# F407.net
KiCad netlist of a schematic drawn in Altium Designer
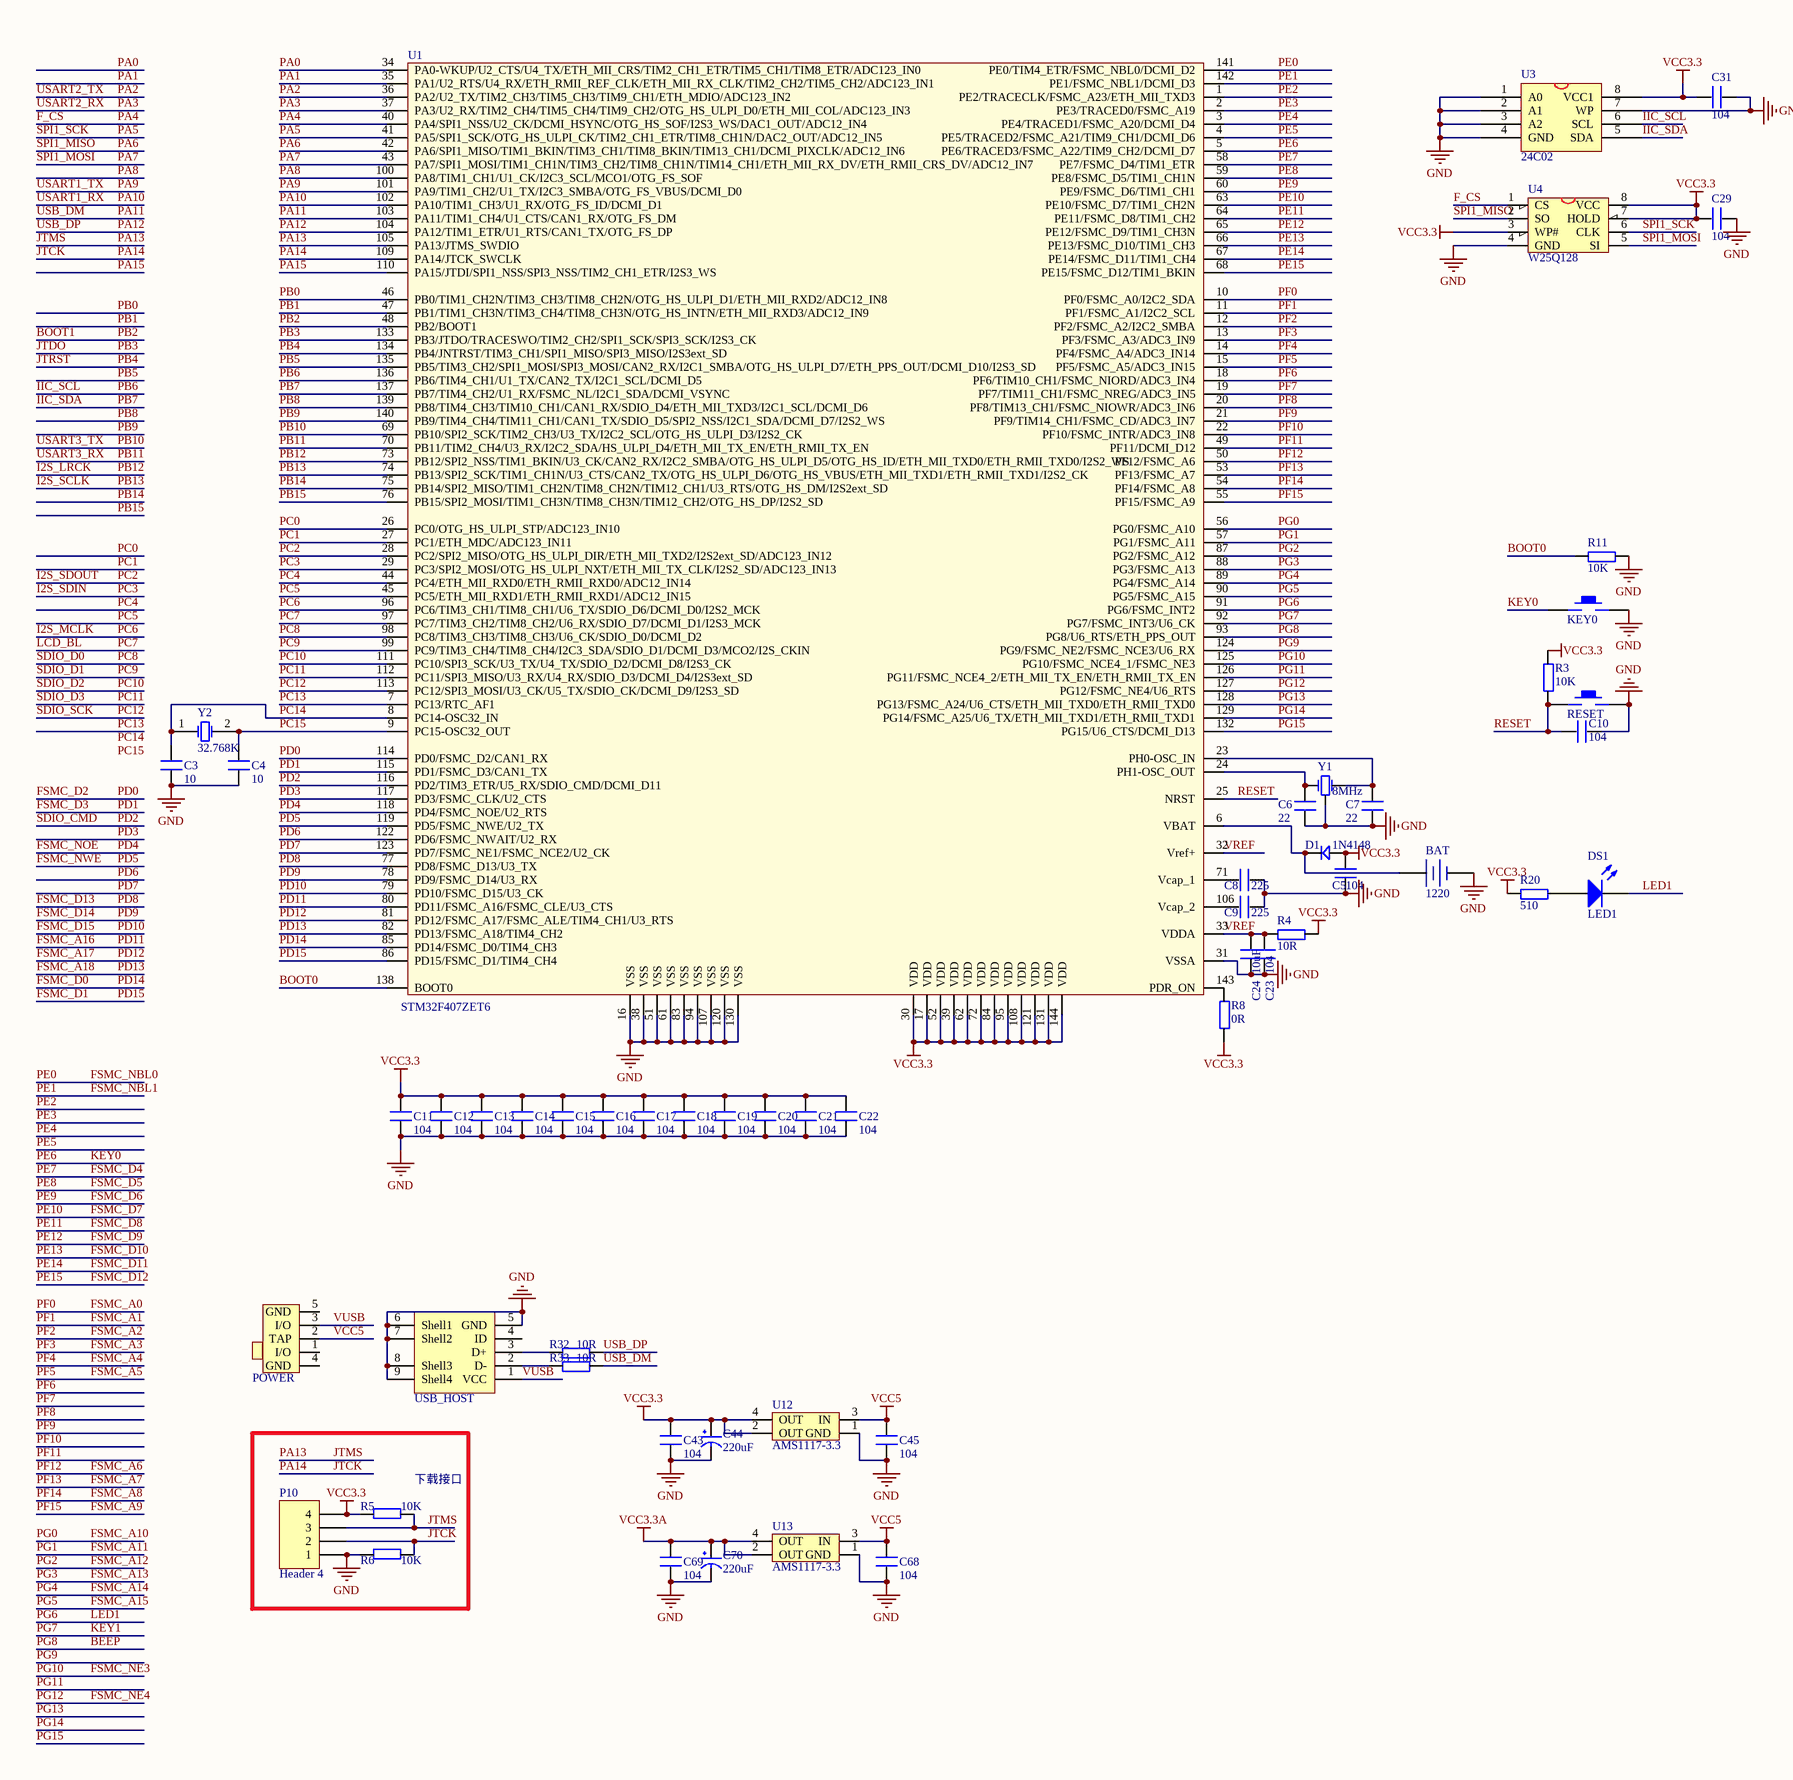
[diagram p0: F407.SchDoc, left]
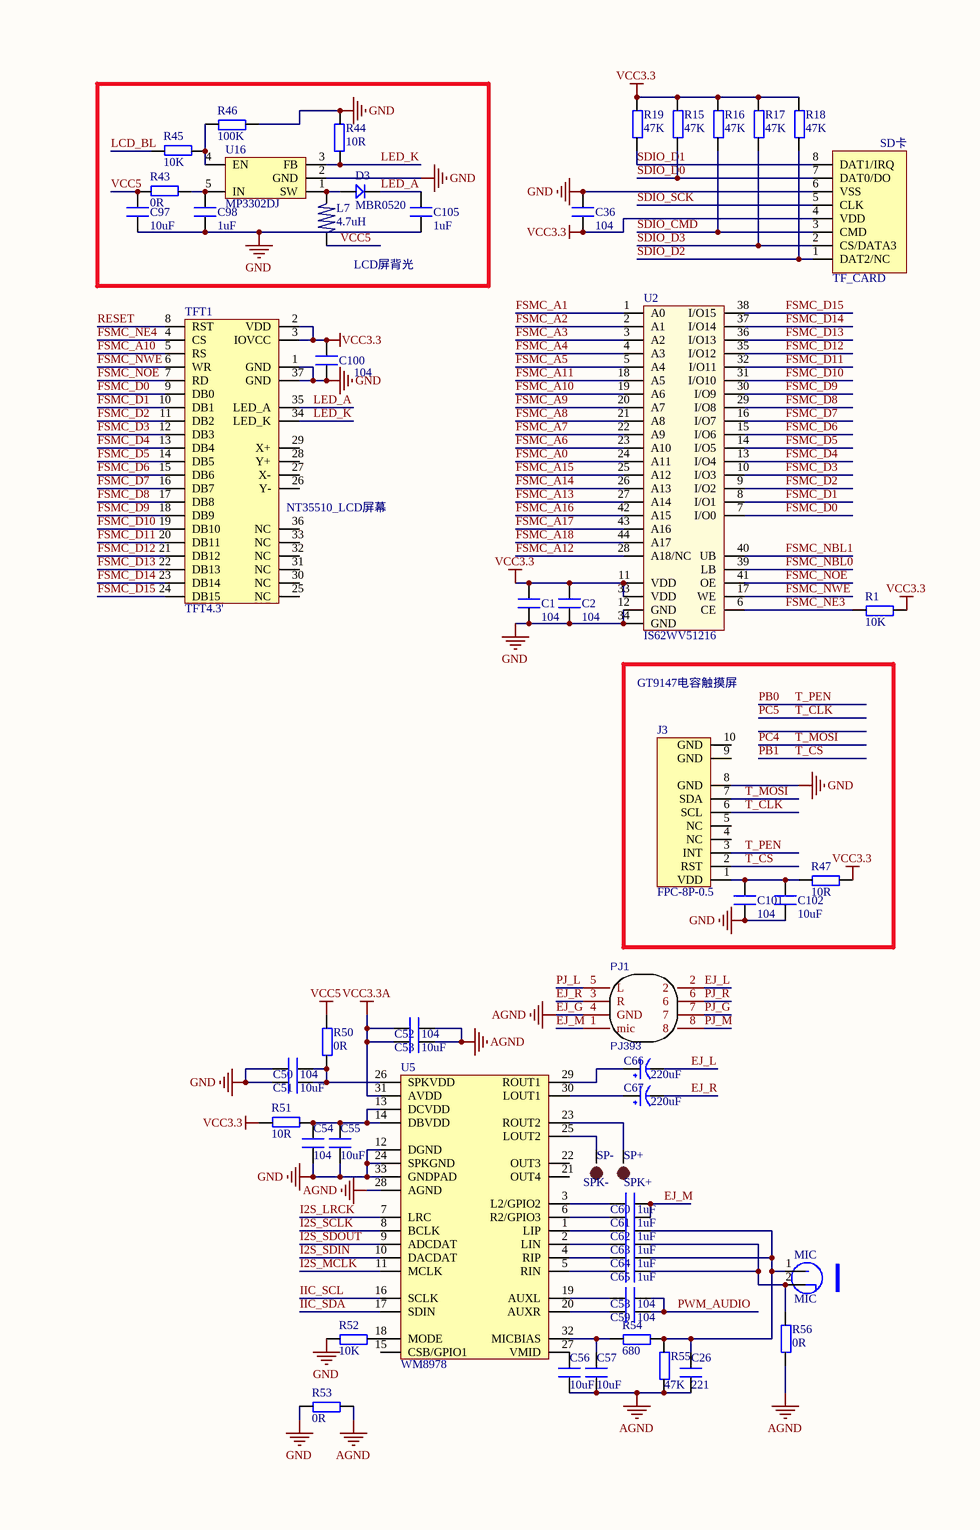
[diagram p1: F407.SchDoc, right]

(export (version "E")
  (design (tool "Eeschema 10.0.6"))
  (components
    (comp (ref "BAT")
      (value "1220")
      (footprint "CR1220_B")
      (description "微型电池")
      (libsource (lib "IMX6UL_ALPHA(底板)_V2.0") (part "CR-3V"))
    )
    (comp (ref "C1")
      (value "104")
      (footprint "C 0603_M")
      (libsource (lib "WarShip V3 STM32103封装库") (part "C"))
    )
    (comp (ref "C2")
      (value "104")
      (footprint "C 0603_M")
      (libsource (lib "WarShip V3 STM32103封装库") (part "C"))
    )
    (comp (ref "C3")
      (value "10")
      (footprint "C 0603_M")
      (libsource (lib "WarShip V3 STM32103封装库") (part "C"))
    )
    (comp (ref "C4")
      (value "10")
      (footprint "C 0603_M")
      (libsource (lib "WarShip V3 STM32103封装库") (part "C"))
    )
    (comp (ref "C5")
      (value "104")
      (footprint "C 0603_M")
      (libsource (lib "WarShip V3 STM32103封装库") (part "C"))
    )
    (comp (ref "C6")
      (value "22")
      (footprint "C 0603_M")
      (libsource (lib "WarShip V3 STM32103封装库") (part "C"))
    )
    (comp (ref "C7")
      (value "22")
      (footprint "C 0603_M")
      (libsource (lib "WarShip V3 STM32103封装库") (part "C"))
    )
    (comp (ref "C8")
      (value "225")
      (footprint "C 0603_M")
      (libsource (lib "WarShip V3 STM32103封装库") (part "C"))
    )
    (comp (ref "C9")
      (value "225")
      (footprint "C 0603_M")
      (libsource (lib "WarShip V3 STM32103封装库") (part "C"))
    )
    (comp (ref "C10")
      (value "104")
      (footprint "C 0603_M")
      (libsource (lib "WarShip V3 STM32103封装库") (part "C"))
    )
    (comp (ref "C11")
      (value "104")
      (footprint "C 0603_M")
      (libsource (lib "WarShip V3 STM32103封装库") (part "C"))
    )
    (comp (ref "C12")
      (value "104")
      (footprint "C 0603_M")
      (libsource (lib "WarShip V3 STM32103封装库") (part "C"))
    )
    (comp (ref "C13")
      (value "104")
      (footprint "C 0603_M")
      (libsource (lib "WarShip V3 STM32103封装库") (part "C"))
    )
    (comp (ref "C14")
      (value "104")
      (footprint "C 0603_M")
      (libsource (lib "WarShip V3 STM32103封装库") (part "C"))
    )
    (comp (ref "C15")
      (value "104")
      (footprint "C 0603_M")
      (libsource (lib "WarShip V3 STM32103封装库") (part "C"))
    )
    (comp (ref "C16")
      (value "104")
      (footprint "C 0603_M")
      (libsource (lib "WarShip V3 STM32103封装库") (part "C"))
    )
    (comp (ref "C17")
      (value "104")
      (footprint "C 0603_M")
      (libsource (lib "WarShip V3 STM32103封装库") (part "C"))
    )
    (comp (ref "C18")
      (value "104")
      (footprint "C 0603_M")
      (libsource (lib "WarShip V3 STM32103封装库") (part "C"))
    )
    (comp (ref "C19")
      (value "104")
      (footprint "C 0603_M")
      (libsource (lib "WarShip V3 STM32103封装库") (part "C"))
    )
    (comp (ref "C20")
      (value "104")
      (footprint "C 0603_M")
      (libsource (lib "WarShip V3 STM32103封装库") (part "C"))
    )
    (comp (ref "C21")
      (value "104")
      (footprint "C 0603_M")
      (libsource (lib "WarShip V3 STM32103封装库") (part "C"))
    )
    (comp (ref "C22")
      (value "104")
      (footprint "C 0603_M")
      (libsource (lib "WarShip V3 STM32103封装库") (part "C"))
    )
    (comp (ref "C23")
      (value "104")
      (footprint "C 0603_M")
      (libsource (lib "WarShip V3 STM32103封装库") (part "C"))
    )
    (comp (ref "C24")
      (value "10uF")
      (footprint "C 0603_M")
      (libsource (lib "WarShip V3 STM32103封装库") (part "C"))
    )
    (comp (ref "C26") (value "221") (footprint "C 0603_M") (libsource (lib "ALIENTEK_COMPONENT") (part "C")))
    (comp (ref "C29")
      (value "104")
      (footprint "C 0603_M")
      (libsource (lib "WarShip V3 STM32103封装库") (part "C"))
    )
    (comp (ref "C31")
      (value "104")
      (footprint "C 0603_M")
      (libsource (lib "WarShip V3 STM32103封装库") (part "C"))
    )
    (comp (ref "C36")
      (value "104")
      (footprint "C 0603_M")
      (libsource (lib "WarShip V3 STM32103封装库") (part "C"))
    )
    (comp (ref "C43")
      (value "104")
      (footprint "C 0603_M")
      (libsource (lib "WarShip V3 STM32103封装库") (part "C"))
    )
    (comp (ref "C44") (value "220uF") (footprint "CT 6*6 - C") (libsource (lib "") (part "CAP_1")))
    (comp (ref "C45")
      (value "104")
      (footprint "C 0603_M")
      (libsource (lib "WarShip V3 STM32103封装库") (part "C"))
    )
    (comp (ref "C50") (value "104") (footprint "C 0603_M") (libsource (lib "ATK-VS1053 MP3") (part "C")))
    (comp (ref "C51") (value "10uF") (footprint "C 0603_M") (libsource (lib "ATK-VS1053 MP3") (part "C")))
    (comp (ref "C52") (value "104") (footprint "C 0603_M") (libsource (lib "ATK-VS1053 MP3") (part "C")))
    (comp (ref "C53") (value "10uF") (footprint "C 0603_M") (libsource (lib "ATK-VS1053 MP3") (part "C")))
    (comp (ref "C54") (value "104") (footprint "C 0603_M") (libsource (lib "ATK-VS1053 MP3") (part "C")))
    (comp (ref "C55") (value "10uF") (footprint "C 0603_M") (libsource (lib "ATK-VS1053 MP3") (part "C")))
    (comp (ref "C56") (value "10uF") (footprint "C 0603_M") (libsource (lib "ATK-VS1053 MP3") (part "C")))
    (comp (ref "C57") (value "10uF") (footprint "C 0603_M") (libsource (lib "ATK-VS1053 MP3") (part "C")))
    (comp (ref "C58") (value "104") (footprint "C 0603_M") (libsource (lib "ATK-VS1053 MP3") (part "C")))
    (comp (ref "C59") (value "104") (footprint "C 0603_M") (libsource (lib "ATK-VS1053 MP3") (part "C")))
    (comp (ref "C60") (value "1uF") (footprint "C 0603_M") (libsource (lib "ATK-VS1053 MP3") (part "C")))
    (comp (ref "C61") (value "1uF") (footprint "C 0603_M") (libsource (lib "ATK-VS1053 MP3") (part "C")))
    (comp (ref "C62") (value "1uF") (footprint "C 0603_M") (libsource (lib "ATK-VS1053 MP3") (part "C")))
    (comp (ref "C63") (value "1uF") (footprint "C 0603_M") (libsource (lib "ATK-VS1053 MP3") (part "C")))
    (comp (ref "C64") (value "1uF") (footprint "C 0603_M") (libsource (lib "ATK-VS1053 MP3") (part "C")))
    (comp (ref "C65") (value "1uF") (footprint "C 0603_M") (libsource (lib "ATK-VS1053 MP3") (part "C")))
    (comp (ref "C66")
      (value "220uF")
      (footprint "CT 6*6 - C")
      (libsource (lib "WarShip V3 STM32103封装库") (part "CAP"))
    )
    (comp (ref "C67")
      (value "220uF")
      (footprint "CT 6*6 - C")
      (libsource (lib "WarShip V3 STM32103封装库") (part "CAP"))
    )
    (comp (ref "C68")
      (value "104")
      (footprint "C 0603_M")
      (libsource (lib "WarShip V3 STM32103封装库") (part "C"))
    )
    (comp (ref "C69")
      (value "104")
      (footprint "C 0603_M")
      (libsource (lib "WarShip V3 STM32103封装库") (part "C"))
    )
    (comp (ref "C70") (value "220uF") (footprint "CT 6*6 - C") (libsource (lib "") (part "CAP_1")))
    (comp (ref "C97") (value "10uF") (footprint "C 0603_M") (libsource (lib "阿波罗STM32F4&F7底板封装库") (part "C")))
    (comp (ref "C98") (value "1uF") (footprint "C 0603_M") (libsource (lib "阿波罗STM32F4&F7底板封装库") (part "C")))
    (comp (ref "C100") (value "104") (footprint "C 0603_M") (libsource (lib "阿波罗STM32F4&F7底板封装库") (part "C")))
    (comp (ref "C101") (value "104") (footprint "C 0603_M") (libsource (lib "阿波罗STM32F4&F7底板封装库") (part "C")))
    (comp (ref "C102")
      (value "10uF")
      (footprint "C 0603_M")
      (libsource (lib "阿波罗STM32F4&F7底板封装库") (part "C"))
    )
    (comp (ref "C105") (value "1uF") (footprint "C 0603_M") (libsource (lib "阿波罗STM32F4&F7底板封装库") (part "C")))
    (comp (ref "D1")
      (value "1N4148")
      (footprint "DIODE_SOP")
      (libsource (lib "WarShip V3 STM32103封装库") (part "D"))
    )
    (comp (ref "D3")
      (value "MBR0520")
      (footprint "SOD-123")
      (description "1N4148")
      (libsource (lib "ATK-4.3' TFTLCD电容触摸屏模块_V1.2") (part "D"))
    )
    (comp (ref "DS1")
      (value "LED1")
      (footprint "LED 0603R")
      (description "Typical RED, GREEN, YELLOW, AMBER GaAs LED")
      (fields (field (name "PUBLISHER") "Altium Limited"))
      (libsource (lib "WarShip V3 STM32103封装库") (part "LED2"))
    )
    (comp (ref "J3")
      (value "FPC-8P-0.5")
      (footprint "FPC-8P")
      (description "FPC-8P-0.5mm")
      (libsource (lib "ATK-4.3' TFTLCD电容触摸屏模块_V1.2") (part "FPC-8"))
    )
    (comp (ref "KEY0")
      (value "KEY_M")
      (footprint "TSW SMD-3*6*2.5")
      (libsource (lib "WarShip V3 STM32103封装库") (part "KEY_M"))
    )
    (comp (ref "L7")
      (value "4.7uH")
      (footprint "L_SOP4")
      (libsource (lib "ATK-4.3' TFTLCD电容触摸屏模块_V1.2") (part "L"))
    )
    (comp (ref "MIC")
      (value "MIC")
      (footprint "MIC-6022")
      (libsource (lib "ALIENTEK_COMPONENT") (part "MIC"))
    )
    (comp (ref "P10")
      (value "Header 4")
      (footprint "HDR2.54-LI-4P")
      (description "Header, 4-Pin")
      (fields (field (name "PUBLISHER") "Altium Limited"))
      (libsource (lib "WarShip V3 STM32103封装库") (part "Header 4"))
    )
    (comp (ref "PJ1")
      (value "PJ393")
      (footprint "PJ393")
      (fields
        (field (name "BOM_MANUFACTURER PART") "?")
        (field (name "CONTRIBUTOR") "infinite_possibilities")
      )
      (libsource (lib "PJ393") (part "PJ393"))
    )
    (comp (ref "POWER")
      (value "BUTTON_DIP3")
      (footprint "MSK-12C01-07")
      (description "拨动开关SS-12F44")
      (libsource (lib "Pandora_STM32L4_Board_V2.4") (part "BUTTON_DIP3"))
    )
    (comp (ref "R1")
      (value "10K")
      (footprint "R 0603_M")
      (libsource (lib "WarShip V3 STM32103封装库") (part "R"))
    )
    (comp (ref "R3")
      (value "10K")
      (footprint "R 0603_M")
      (libsource (lib "WarShip V3 STM32103封装库") (part "R"))
    )
    (comp (ref "R4")
      (value "10R")
      (footprint "R 0603_M")
      (libsource (lib "WarShip V3 STM32103封装库") (part "R"))
    )
    (comp (ref "R5")
      (value "10K")
      (footprint "R 0603_M")
      (libsource (lib "WarShip V3 STM32103封装库") (part "R"))
    )
    (comp (ref "R6")
      (value "10K")
      (footprint "R 0603_M")
      (libsource (lib "WarShip V3 STM32103封装库") (part "R"))
    )
    (comp (ref "R8")
      (value "0R")
      (footprint "R 0603_M")
      (libsource (lib "WarShip V3 STM32103封装库") (part "R"))
    )
    (comp (ref "R11")
      (value "10K")
      (footprint "R 0603_M")
      (libsource (lib "WarShip V3 STM32103封装库") (part "R"))
    )
    (comp (ref "R15")
      (value "47K")
      (footprint "R 0603_M")
      (libsource (lib "WarShip V3 STM32103封装库") (part "R"))
    )
    (comp (ref "R16")
      (value "47K")
      (footprint "R 0603_M")
      (libsource (lib "WarShip V3 STM32103封装库") (part "R"))
    )
    (comp (ref "R17")
      (value "47K")
      (footprint "R 0603_M")
      (libsource (lib "WarShip V3 STM32103封装库") (part "R"))
    )
    (comp (ref "R18")
      (value "47K")
      (footprint "R 0603_M")
      (libsource (lib "WarShip V3 STM32103封装库") (part "R"))
    )
    (comp (ref "R19")
      (value "47K")
      (footprint "R 0603_M")
      (libsource (lib "WarShip V3 STM32103封装库") (part "R"))
    )
    (comp (ref "R20")
      (value "510")
      (footprint "R 0603_M")
      (libsource (lib "WarShip V3 STM32103封装库") (part "R"))
    )
    (comp (ref "R32")
      (value "10R")
      (footprint "R 0603_M")
      (libsource (lib "WarShip V3 STM32103封装库") (part "R"))
    )
    (comp (ref "R33")
      (value "10R")
      (footprint "R 0603_M")
      (libsource (lib "WarShip V3 STM32103封装库") (part "R"))
    )
    (comp (ref "R43") (value "0R") (footprint "R 0603_M") (libsource (lib "阿波罗STM32F4&F7底板封装库") (part "R")))
    (comp (ref "R44") (value "10R") (footprint "R 0603_M") (libsource (lib "阿波罗STM32F4&F7底板封装库") (part "R")))
    (comp (ref "R45") (value "10K") (footprint "R 0603_M") (libsource (lib "阿波罗STM32F4&F7底板封装库") (part "R")))
    (comp (ref "R46") (value "100K") (footprint "R 0603_M") (libsource (lib "阿波罗STM32F4&F7底板封装库") (part "R")))
    (comp (ref "R47") (value "10R") (footprint "R 0603_M") (libsource (lib "阿波罗STM32F4&F7底板封装库") (part "R")))
    (comp (ref "R50") (value "0R") (footprint "R 0603_M") (libsource (lib "ATK-VS1053 MP3") (part "R")))
    (comp (ref "R51") (value "10R") (footprint "R 0603_M") (libsource (lib "ATK-VS1053 MP3") (part "R")))
    (comp (ref "R52") (value "10K") (footprint "R 0603_M") (libsource (lib "ATK-VS1053 MP3") (part "R")))
    (comp (ref "R53") (value "0R") (footprint "R 0603_M") (libsource (lib "ATK-VS1053 MP3") (part "R")))
    (comp (ref "R54") (value "680") (footprint "R 0603_M") (libsource (lib "ATK-VS1053 MP3") (part "R")))
    (comp (ref "R55") (value "47K") (footprint "R 0603_M") (libsource (lib "ATK-VS1053 MP3") (part "R")))
    (comp (ref "R56") (value "0R") (footprint "R 0603_M") (libsource (lib "ATK-VS1053 MP3") (part "R")))
    (comp (ref "RESET")
      (value "KEY_M")
      (footprint "TSW SMD-3*6*2.5")
      (libsource (lib "WarShip V3 STM32103封装库") (part "KEY_M"))
    )
    (comp (ref "SP+")
      (value "SPK+")
      (footprint "TP-1.5")
      (description "测试点")
      (libsource (lib "ALIENTEK_COMPONENT") (part "TEST-POINT"))
    )
    (comp (ref "SP-")
      (value "SPK-")
      (footprint "TP-1.5")
      (description "测试点")
      (libsource (lib "ALIENTEK_COMPONENT") (part "TEST-POINT"))
    )
    (comp (ref "TFT1")
      (value "TFT4.3'")
      (footprint "TFT4.3'")
      (description "4.3寸,电容/电阻触摸,分辨率:480*800")
      (libsource (lib "ATK-4.3' TFTLCD电容触摸屏模块_V1.2") (part "TFT4.3‘"))
    )
    (comp (ref "TF_CARD")
      (value "SD-MICRO-TF")
      (footprint "SD-MICRO-TF")
      (description "SD,MICRO,TF")
      (libsource (lib "Pandora_STM32L4_Board_V2.4") (part "SD-MICRO-TF"))
    )
    (comp (ref "U1")
      (value "STM32F407ZET6")
      (footprint "LQFP144")
      (libsource (lib "Explorer STM32F407封装库") (part "STM32F407ZET6"))
    )
    (comp (ref "U2")
      (value "IS62WV51216")
      (footprint "TSOP44")
      (libsource (lib "WarShip V3 STM32103封装库") (part "IS61LV51216"))
    )
    (comp (ref "U3")
      (value "24C02")
      (footprint "SOP-8")
      (libsource (lib "WarShip V3 STM32103封装库") (part "24C256"))
    )
    (comp (ref "U4")
      (value "W25Q128")
      (footprint "SOIC-8")
      (description "W25X16;SST25VF016;MX25L1605")
      (libsource (lib "WarShip V3 STM32103封装库") (part "W25X16"))
    )
    (comp (ref "U5")
      (value "WM8978")
      (footprint "qfn32")
      (description "24bit ADC&DAC")
      (libsource (lib "ALIENTEK_COMPONENT") (part "WM8978"))
    )
    (comp (ref "U12")
      (value "AMS1117-3.3")
      (footprint "AMS1117")
      (libsource (lib "WarShip V3 STM32103封装库") (part "AMS1117"))
    )
    (comp (ref "U13")
      (value "AMS1117-3.3")
      (footprint "AMS1117")
      (libsource (lib "WarShip V3 STM32103封装库") (part "AMS1117"))
    )
    (comp (ref "U16")
      (value "MP3302DJ")
      (footprint "SOT-23-5")
      (description "LCD背光IC")
      (libsource (lib "ATK-4.3' TFTLCD电容触摸屏模块_V1.2") (part "MP3302"))
    )
    (comp (ref "USB_HOST")
      (value "J-MICRO-USB-5S")
      (footprint "USB-AB-5S")
      (description "Micro USB 5.9有柱脚长1.25加长针")
      (libsource (lib "Pandora_STM32L4_Board_V2.4") (part "J-MICRO-USB-5S"))
    )
    (comp (ref "Y1")
      (value "8MHz")
      (footprint "Y-XTAL-3215-3P")
      (description "XTAL,3215,8MHz")
      (libsource (lib "Pandora_STM32L4_Board_V2.4") (part "Y-3215-8M"))
    )
    (comp (ref "Y2")
      (value "32.768K")
      (footprint "Y-XTAL-3215-2P")
      (description "Crystal Oscillator")
      (fields (field (name "PUBLISHER") "Altium Limited"))
      (libsource (lib "WarShip V3 STM32103封装库") (part "XTAL"))
    )
  )
  (nets
    (net (code "1") (name "/BEEP") (class "Default")
      (node (ref "U1") (pin "93") (pinfunction "PG8/U6_RTS/ETH_PPS_OUT_93") (pintype "passive"))
    )
    (net (code "2") (name "/BOOT0") (class "Default")
      (node (ref "R11") (pin "1") (pintype "passive"))
      (node (ref "U1") (pin "138") (pinfunction "BOOT0_138") (pintype "passive"))
    )
    (net (code "3") (name "/BOOT1") (class "Default")
      (node (ref "U1") (pin "48") (pinfunction "PB2/BOOT1_48") (pintype "passive"))
    )
    (net (code "4") (name "/EJ_L") (class "Default")
      (node (ref "C66") (pin "2") (pinfunction "GND_2") (pintype "passive"))
      (node (ref "PJ1") (pin "2") (pinfunction "2_2") (pintype "passive"))
    )
    (net (code "5") (name "/EJ_M") (class "Default")
      (node (ref "C60") (pin "2") (pintype "passive"))
      (node (ref "C61") (pin "2") (pintype "passive"))
      (node (ref "PJ1") (pin "1") (pinfunction "mic_1") (pintype "passive"))
    )
    (net (code "6") (name "/EJ_R") (class "Default")
      (node (ref "C67") (pin "2") (pinfunction "GND_2") (pintype "passive"))
      (node (ref "PJ1") (pin "3") (pinfunction "R_3") (pintype "passive"))
    )
    (net (code "7") (name "/FSMC_A0") (class "Default")
      (node (ref "U1") (pin "10") (pinfunction "PF0/FSMC_A0/I2C2_SDA_10") (pintype "passive"))
      (node (ref "U2") (pin "24") (pinfunction "A11_24") (pintype "passive"))
    )
    (net (code "8") (name "/FSMC_A1") (class "Default")
      (node (ref "U1") (pin "11") (pinfunction "PF1/FSMC_A1/I2C2_SCL_11") (pintype "passive"))
      (node (ref "U2") (pin "1") (pinfunction "A0_1") (pintype "passive"))
    )
    (net (code "9") (name "/FSMC_A2") (class "Default")
      (node (ref "U1") (pin "12") (pinfunction "PF2/FSMC_A2/I2C2_SMBA_12") (pintype "passive"))
      (node (ref "U2") (pin "2") (pinfunction "A1_2") (pintype "passive"))
    )
    (net (code "10") (name "/FSMC_A3") (class "Default")
      (node (ref "U1") (pin "13") (pinfunction "PF3/FSMC_A3/ADC3_IN9_13") (pintype "passive"))
      (node (ref "U2") (pin "3") (pinfunction "A2_3") (pintype "passive"))
    )
    (net (code "11") (name "/FSMC_A4") (class "Default")
      (node (ref "U1") (pin "14") (pinfunction "PF4/FSMC_A4/ADC3_IN14_14") (pintype "passive"))
      (node (ref "U2") (pin "4") (pinfunction "A3_4") (pintype "passive"))
    )
    (net (code "12") (name "/FSMC_A5") (class "Default")
      (node (ref "U1") (pin "15") (pinfunction "PF5/FSMC_A5/ADC3_IN15_15") (pintype "passive"))
      (node (ref "U2") (pin "5") (pinfunction "A4_5") (pintype "passive"))
    )
    (net (code "13") (name "/FSMC_A6") (class "Default")
      (node (ref "U1") (pin "50") (pinfunction "PF12/FSMC_A6_50") (pintype "passive"))
      (node (ref "U2") (pin "23") (pinfunction "A10_23") (pintype "passive"))
    )
    (net (code "14") (name "/FSMC_A7") (class "Default")
      (node (ref "U1") (pin "53") (pinfunction "PF13/FSMC_A7_53") (pintype "passive"))
      (node (ref "U2") (pin "22") (pinfunction "A9_22") (pintype "passive"))
    )
    (net (code "15") (name "/FSMC_A8") (class "Default")
      (node (ref "U1") (pin "54") (pinfunction "PF14/FSMC_A8_54") (pintype "passive"))
      (node (ref "U2") (pin "21") (pinfunction "A8_21") (pintype "passive"))
    )
    (net (code "16") (name "/FSMC_A9") (class "Default")
      (node (ref "U1") (pin "55") (pinfunction "PF15/FSMC_A9_55") (pintype "passive"))
      (node (ref "U2") (pin "20") (pinfunction "A7_20") (pintype "passive"))
    )
    (net (code "17") (name "/FSMC_A10") (class "Default")
      (node (ref "TFT1") (pin "5") (pinfunction "RS_5") (pintype "passive"))
      (node (ref "U1") (pin "56") (pinfunction "PG0/FSMC_A10_56") (pintype "passive"))
      (node (ref "U2") (pin "19") (pinfunction "A6_19") (pintype "passive"))
    )
    (net (code "18") (name "/FSMC_A11") (class "Default")
      (node (ref "U1") (pin "57") (pinfunction "PG1/FSMC_A11_57") (pintype "passive"))
      (node (ref "U2") (pin "18") (pinfunction "A5_18") (pintype "passive"))
    )
    (net (code "19") (name "/FSMC_A12") (class "Default")
      (node (ref "U1") (pin "87") (pinfunction "PG2/FSMC_A12_87") (pintype "passive"))
      (node (ref "U2") (pin "28") (pinfunction "A18/NC_28") (pintype "passive"))
    )
    (net (code "20") (name "/FSMC_A13") (class "Default")
      (node (ref "U1") (pin "88") (pinfunction "PG3/FSMC_A13_88") (pintype "passive"))
      (node (ref "U2") (pin "27") (pinfunction "A14_27") (pintype "passive"))
    )
    (net (code "21") (name "/FSMC_A14") (class "Default")
      (node (ref "U1") (pin "89") (pinfunction "PG4/FSMC_A14_89") (pintype "passive"))
      (node (ref "U2") (pin "26") (pinfunction "A13_26") (pintype "passive"))
    )
    (net (code "22") (name "/FSMC_A15") (class "Default")
      (node (ref "U1") (pin "90") (pinfunction "PG5/FSMC_A15_90") (pintype "passive"))
      (node (ref "U2") (pin "25") (pinfunction "A12_25") (pintype "passive"))
    )
    (net (code "23") (name "/FSMC_A16") (class "Default")
      (node (ref "U1") (pin "80") (pinfunction "PD11/FSMC_A16/FSMC_CLE/U3_CTS_80") (pintype "passive"))
      (node (ref "U2") (pin "42") (pinfunction "A15_42") (pintype "passive"))
    )
    (net (code "24") (name "/FSMC_A17") (class "Default")
      (node (ref "U1") (pin "81") (pinfunction "PD12/FSMC_A17/FSMC_ALE/TIM4_CH1/U3_RTS_81") (pintype "passive"))
      (node (ref "U2") (pin "43") (pinfunction "A16_43") (pintype "passive"))
    )
    (net (code "25") (name "/FSMC_A18") (class "Default")
      (node (ref "U1") (pin "82") (pinfunction "PD13/FSMC_A18/TIM4_CH2_82") (pintype "passive"))
      (node (ref "U2") (pin "44") (pinfunction "A17_44") (pintype "passive"))
    )
    (net (code "26") (name "/FSMC_D0") (class "Default")
      (node (ref "TFT1") (pin "9") (pinfunction "DB0_9") (pintype "passive"))
      (node (ref "U1") (pin "85") (pinfunction "PD14/FSMC_D0/TIM4_CH3_85") (pintype "passive"))
      (node (ref "U2") (pin "7") (pinfunction "I/O0_7") (pintype "passive"))
    )
    (net (code "27") (name "/FSMC_D1") (class "Default")
      (node (ref "TFT1") (pin "10") (pinfunction "DB1_10") (pintype "passive"))
      (node (ref "U1") (pin "86") (pinfunction "PD15/FSMC_D1/TIM4_CH4_86") (pintype "passive"))
      (node (ref "U2") (pin "8") (pinfunction "I/O1_8") (pintype "passive"))
    )
    (net (code "28") (name "/FSMC_D2") (class "Default")
      (node (ref "TFT1") (pin "11") (pinfunction "DB2_11") (pintype "passive"))
      (node (ref "U1") (pin "114") (pinfunction "PD0/FSMC_D2/CAN1_RX_114") (pintype "passive"))
      (node (ref "U2") (pin "9") (pinfunction "I/O2_9") (pintype "passive"))
    )
    (net (code "29") (name "/FSMC_D3") (class "Default")
      (node (ref "TFT1") (pin "12") (pinfunction "DB3_12") (pintype "passive"))
      (node (ref "U1") (pin "115") (pinfunction "PD1/FSMC_D3/CAN1_TX_115") (pintype "passive"))
      (node (ref "U2") (pin "10") (pinfunction "I/O3_10") (pintype "passive"))
    )
    (net (code "30") (name "/FSMC_D4") (class "Default")
      (node (ref "TFT1") (pin "13") (pinfunction "DB4_13") (pintype "passive"))
      (node (ref "U1") (pin "58") (pinfunction "PE7/FSMC_D4/TIM1_ETR_58") (pintype "passive"))
      (node (ref "U2") (pin "13") (pinfunction "I/O4_13") (pintype "passive"))
    )
    (net (code "31") (name "/FSMC_D5") (class "Default")
      (node (ref "TFT1") (pin "14") (pinfunction "DB5_14") (pintype "passive"))
      (node (ref "U1") (pin "59") (pinfunction "PE8/FSMC_D5/TIM1_CH1N_59") (pintype "passive"))
      (node (ref "U2") (pin "14") (pinfunction "I/O5_14") (pintype "passive"))
    )
    (net (code "32") (name "/FSMC_D6") (class "Default")
      (node (ref "TFT1") (pin "15") (pinfunction "DB6_15") (pintype "passive"))
      (node (ref "U1") (pin "60") (pinfunction "PE9/FSMC_D6/TIM1_CH1_60") (pintype "passive"))
      (node (ref "U2") (pin "15") (pinfunction "I/O6_15") (pintype "passive"))
    )
    (net (code "33") (name "/FSMC_D7") (class "Default")
      (node (ref "TFT1") (pin "16") (pinfunction "DB7_16") (pintype "passive"))
      (node (ref "U1") (pin "63") (pinfunction "PE10/FSMC_D7/TIM1_CH2N_63") (pintype "passive"))
      (node (ref "U2") (pin "16") (pinfunction "I/O7_16") (pintype "passive"))
    )
    (net (code "34") (name "/FSMC_D8") (class "Default")
      (node (ref "TFT1") (pin "17") (pinfunction "DB8_17") (pintype "passive"))
      (node (ref "U1") (pin "64") (pinfunction "PE11/FSMC_D8/TIM1_CH2_64") (pintype "passive"))
      (node (ref "U2") (pin "29") (pinfunction "I/O8_29") (pintype "passive"))
    )
    (net (code "35") (name "/FSMC_D9") (class "Default")
      (node (ref "TFT1") (pin "18") (pinfunction "DB9_18") (pintype "passive"))
      (node (ref "U1") (pin "65") (pinfunction "PE12/FSMC_D9/TIM1_CH3N_65") (pintype "passive"))
      (node (ref "U2") (pin "30") (pinfunction "I/O9_30") (pintype "passive"))
    )
    (net (code "36") (name "/FSMC_D10") (class "Default")
      (node (ref "TFT1") (pin "19") (pinfunction "DB10_19") (pintype "passive"))
      (node (ref "U1") (pin "66") (pinfunction "PE13/FSMC_D10/TIM1_CH3_66") (pintype "passive"))
      (node (ref "U2") (pin "31") (pinfunction "I/O10_31") (pintype "passive"))
    )
    (net (code "37") (name "/FSMC_D11") (class "Default")
      (node (ref "TFT1") (pin "20") (pinfunction "DB11_20") (pintype "passive"))
      (node (ref "U1") (pin "67") (pinfunction "PE14/FSMC_D11/TIM1_CH4_67") (pintype "passive"))
      (node (ref "U2") (pin "32") (pinfunction "I/O11_32") (pintype "passive"))
    )
    (net (code "38") (name "/FSMC_D12") (class "Default")
      (node (ref "TFT1") (pin "21") (pinfunction "DB12_21") (pintype "passive"))
      (node (ref "U1") (pin "68") (pinfunction "PE15/FSMC_D12/TIM1_BKIN_68") (pintype "passive"))
      (node (ref "U2") (pin "35") (pinfunction "I/O12_35") (pintype "passive"))
    )
    (net (code "39") (name "/FSMC_D13") (class "Default")
      (node (ref "TFT1") (pin "22") (pinfunction "DB13_22") (pintype "passive"))
      (node (ref "U1") (pin "77") (pinfunction "PD8/FSMC_D13/U3_TX_77") (pintype "passive"))
      (node (ref "U2") (pin "36") (pinfunction "I/O13_36") (pintype "passive"))
    )
    (net (code "40") (name "/FSMC_D14") (class "Default")
      (node (ref "TFT1") (pin "23") (pinfunction "DB14_23") (pintype "passive"))
      (node (ref "U1") (pin "78") (pinfunction "PD9/FSMC_D14/U3_RX_78") (pintype "passive"))
      (node (ref "U2") (pin "37") (pinfunction "I/O14_37") (pintype "passive"))
    )
    (net (code "41") (name "/FSMC_D15") (class "Default")
      (node (ref "TFT1") (pin "24") (pinfunction "DB15_24") (pintype "passive"))
      (node (ref "U1") (pin "79") (pinfunction "PD10/FSMC_D15/U3_CK_79") (pintype "passive"))
      (node (ref "U2") (pin "38") (pinfunction "I/O15_38") (pintype "passive"))
    )
    (net (code "42") (name "/FSMC_NBL0") (class "Default")
      (node (ref "U1") (pin "141") (pinfunction "PE0/TIM4_ETR/FSMC_NBL0/DCMI_D2_141") (pintype "passive"))
      (node (ref "U2") (pin "39") (pinfunction "LB_39") (pintype "passive"))
    )
    (net (code "43") (name "/FSMC_NBL1") (class "Default")
      (node (ref "U1") (pin "142") (pinfunction "PE1/FSMC_NBL1/DCMI_D3_142") (pintype "passive"))
      (node (ref "U2") (pin "40") (pinfunction "UB_40") (pintype "passive"))
    )
    (net (code "44") (name "/FSMC_NE3") (class "Default")
      (node (ref "R1") (pin "1") (pintype "passive"))
      (node (ref "U1") (pin "125") (pinfunction "PG10/FSMC_NCE4_1/FSMC_NE3_125") (pintype "passive"))
      (node (ref "U2") (pin "6") (pinfunction "CE_6") (pintype "passive"))
    )
    (net (code "45") (name "/FSMC_NE4") (class "Default")
      (node (ref "TFT1") (pin "4") (pinfunction "CS_4") (pintype "passive"))
      (node (ref "U1") (pin "127") (pinfunction "PG12/FSMC_NE4/U6_RTS_127") (pintype "passive"))
    )
    (net (code "46") (name "/FSMC_NOE") (class "Default")
      (node (ref "TFT1") (pin "7") (pinfunction "RD_7") (pintype "passive"))
      (node (ref "U1") (pin "118") (pinfunction "PD4/FSMC_NOE/U2_RTS_118") (pintype "passive"))
      (node (ref "U2") (pin "41") (pinfunction "OE_41") (pintype "passive"))
    )
    (net (code "47") (name "/FSMC_NWE") (class "Default")
      (node (ref "TFT1") (pin "6") (pinfunction "WR_6") (pintype "passive"))
      (node (ref "U1") (pin "119") (pinfunction "PD5/FSMC_NWE/U2_TX_119") (pintype "passive"))
      (node (ref "U2") (pin "17") (pinfunction "WE_17") (pintype "passive"))
    )
    (net (code "48") (name "/F_CS") (class "Default")
      (node (ref "U1") (pin "40") (pinfunction "PA4/SPI1_NSS/U2_CK/DCMI_HSYNC/OTG_HS_SOF/I2S3_WS/DAC1_OUT/ADC12_IN4_40") (pintype "passive"))
      (node (ref "U4") (pin "1") (pinfunction "CS_1") (pintype "passive"))
    )
    (net (code "49") (name "/I2S_LRCK") (class "Default")
      (node (ref "U1") (pin "73") (pinfunction "PB12/SPI2_NSS/TIM1_BKIN/U3_CK/CAN2_RX/I2C2_SMBA/OTG_HS_ULPI_D5/OTG_HS_ID/ETH_MII_TXD0/ETH_RMII_TXD0/I2S2_WS_73") (pintype "passive"))
      (node (ref "U5") (pin "7") (pinfunction "LRC_7") (pintype "passive"))
    )
    (net (code "50") (name "/I2S_MCLK") (class "Default")
      (node (ref "U1") (pin "96") (pinfunction "PC6/TIM3_CH1/TIM8_CH1/U6_TX/SDIO_D6/DCMI_D0/I2S2_MCK_96") (pintype "passive"))
      (node (ref "U5") (pin "11") (pinfunction "MCLK_11") (pintype "passive"))
    )
    (net (code "51") (name "/I2S_SCLK") (class "Default")
      (node (ref "U1") (pin "74") (pinfunction "PB13/SPI2_SCK/TIM1_CH1N/U3_CTS/CAN2_TX/OTG_HS_ULPI_D6/OTG_HS_VBUS/ETH_MII_TXD1/ETH_RMII_TXD1/I2S2_CK_74") (pintype "passive"))
      (node (ref "U5") (pin "8") (pinfunction "BCLK_8") (pintype "passive"))
    )
    (net (code "52") (name "/I2S_SDIN") (class "Default")
      (node (ref "U1") (pin "29") (pinfunction "PC3/SPI2_MOSI/OTG_HS_ULPI_NXT/ETH_MII_TX_CLK/I2S2_SD/ADC123_IN13_29") (pintype "passive"))
      (node (ref "U5") (pin "10") (pinfunction "DACDAT_10") (pintype "passive"))
    )
    (net (code "53") (name "/I2S_SDOUT") (class "Default")
      (node (ref "U1") (pin "28") (pinfunction "PC2/SPI2_MISO/OTG_HS_ULPI_DIR/ETH_MII_TXD2/I2S2ext_SD/ADC123_IN12_28") (pintype "passive"))
      (node (ref "U5") (pin "9") (pinfunction "ADCDAT_9") (pintype "passive"))
    )
    (net (code "54") (name "/IIC_SCL") (class "Default")
      (node (ref "U1") (pin "136") (pinfunction "PB6/TIM4_CH1/U1_TX/CAN2_TX/I2C1_SCL/DCMI_D5_136") (pintype "passive"))
      (node (ref "U3") (pin "6") (pinfunction "SCL_6") (pintype "passive"))
      (node (ref "U5") (pin "16") (pinfunction "SCLK_16") (pintype "passive"))
    )
    (net (code "55") (name "/IIC_SDA") (class "Default")
      (node (ref "U1") (pin "137") (pinfunction "PB7/TIM4_CH2/U1_RX/FSMC_NL/I2C1_SDA/DCMI_VSYNC_137") (pintype "passive"))
      (node (ref "U3") (pin "5") (pinfunction "SDA_5") (pintype "passive"))
      (node (ref "U5") (pin "17") (pinfunction "SDIN_17") (pintype "passive"))
    )
    (net (code "56") (name "/JTCK") (class "Default")
      (node (ref "P10") (pin "2") (pinfunction "2_2") (pintype "passive"))
      (node (ref "R6") (pin "1") (pintype "passive"))
      (node (ref "U1") (pin "109") (pinfunction "PA14/JTCK_SWCLK_109") (pintype "passive"))
    )
    (net (code "57") (name "/JTDO") (class "Default")
      (node (ref "U1") (pin "133") (pinfunction "PB3/JTDO/TRACESWO/TIM2_CH2/SPI1_SCK/SPI3_SCK/I2S3_CK_133") (pintype "passive"))
    )
    (net (code "58") (name "/JTMS") (class "Default")
      (node (ref "P10") (pin "3") (pinfunction "3_3") (pintype "passive"))
      (node (ref "R5") (pin "1") (pintype "passive"))
      (node (ref "U1") (pin "105") (pinfunction "PA13/JTMS_SWDIO_105") (pintype "passive"))
    )
    (net (code "59") (name "/JTRST") (class "Default")
      (node (ref "U1") (pin "134") (pinfunction "PB4/JNTRST/TIM3_CH1/SPI1_MISO/SPI3_MISO/I2S3ext_SD_134") (pintype "passive"))
    )
    (net (code "60") (name "/KEY0") (class "Default")
      (node (ref "KEY0") (pin "1") (pinfunction "1_1") (pintype "passive"))
      (node (ref "U1") (pin "5") (pinfunction "PE6/TRACED3/FSMC_A22/TIM9_CH2/DCMI_D7_5") (pintype "passive"))
    )
    (net (code "61") (name "/KEY1") (class "Default")
      (node (ref "U1") (pin "92") (pinfunction "PG7/FSMC_INT3/U6_CK_92") (pintype "passive"))
    )
    (net (code "62") (name "/LCD_BL") (class "Default")
      (node (ref "R45") (pin "2") (pintype "passive"))
      (node (ref "U1") (pin "97") (pinfunction "PC7/TIM3_CH2/TIM8_CH2/U6_RX/SDIO_D7/DCMI_D1/I2S3_MCK_97") (pintype "passive"))
    )
    (net (code "63") (name "/LED1") (class "Default")
      (node (ref "DS1") (pin "2") (pinfunction "K_2") (pintype "passive"))
      (node (ref "U1") (pin "91") (pinfunction "PG6/FSMC_INT2_91") (pintype "passive"))
    )
    (net (code "64") (name "/LED_A") (class "Default")
      (node (ref "C105") (pin "1") (pintype "passive"))
      (node (ref "D3") (pin "2") (pintype "passive"))
      (node (ref "TFT1") (pin "35") (pinfunction "LED_A_35") (pintype "passive"))
    )
    (net (code "65") (name "/LED_K") (class "Default")
      (node (ref "R44") (pin "2") (pintype "passive"))
      (node (ref "TFT1") (pin "34") (pinfunction "LED_K_34") (pintype "passive"))
      (node (ref "U16") (pin "3") (pinfunction "FB_3") (pintype "passive"))
    )
    (net (code "66") (name "/PA0") (class "Default")
      (node (ref "U1") (pin "34") (pinfunction "PA0-WKUP/U2_CTS/U4_TX/ETH_MII_CRS/TIM2_CH1_ETR/TIM5_CH1/TIM8_ETR/ADC123_IN0_34") (pintype "passive"))
    )
    (net (code "67") (name "/PA1") (class "Default")
      (node (ref "U1") (pin "35") (pinfunction "PA1/U2_RTS/U4_RX/ETH_RMII_REF_CLK/ETH_MII_RX_CLK/TIM2_CH2/TIM5_CH2/ADC123_IN1_35") (pintype "passive"))
    )
    (net (code "68") (name "/PA2") (class "Default")
      (node (ref "U1") (pin "36") (pinfunction "PA2/U2_TX/TIM2_CH3/TIM5_CH3/TIM9_CH1/ETH_MDIO/ADC123_IN2_36") (pintype "passive"))
    )
    (net (code "69") (name "/PA3") (class "Default")
      (node (ref "U1") (pin "37") (pinfunction "PA3/U2_RX/TIM2_CH4/TIM5_CH4/TIM9_CH2/OTG_HS_ULPI_D0/ETH_MII_COL/ADC123_IN3_37") (pintype "passive"))
    )
    (net (code "70") (name "/PA5") (class "Default")
      (node (ref "U1") (pin "41") (pinfunction "PA5/SPI1_SCK/OTG_HS_ULPI_CK/TIM2_CH1_ETR/TIM8_CH1N/DAC2_OUT/ADC12_IN5_41") (pintype "passive"))
      (node (ref "U4") (pin "6") (pinfunction "CLK_6") (pintype "passive"))
    )
    (net (code "71") (name "/PA6") (class "Default")
      (node (ref "U1") (pin "42") (pinfunction "PA6/SPI1_MISO/TIM1_BKIN/TIM3_CH1/TIM8_BKIN/TIM13_CH1/DCMI_PIXCLK/ADC12_IN6_42") (pintype "passive"))
      (node (ref "U4") (pin "2") (pinfunction "SO_2") (pintype "passive"))
    )
    (net (code "72") (name "/PA7") (class "Default")
      (node (ref "U1") (pin "43") (pinfunction "PA7/SPI1_MOSI/TIM1_CH1N/TIM3_CH2/TIM8_CH1N/TIM14_CH1/ETH_MII_RX_DV/ETH_RMII_CRS_DV/ADC12_IN7_43") (pintype "passive"))
      (node (ref "U4") (pin "5") (pinfunction "SI_5") (pintype "passive"))
    )
    (net (code "73") (name "/PA8") (class "Default")
      (node (ref "U1") (pin "100") (pinfunction "PA8/TIM1_CH1/U1_CK/I2C3_SCL/MCO1/OTG_FS_SOF_100") (pintype "passive"))
    )
    (net (code "74") (name "/PA9") (class "Default")
      (node (ref "U1") (pin "101") (pinfunction "PA9/TIM1_CH2/U1_TX/I2C3_SMBA/OTG_FS_VBUS/DCMI_D0_101") (pintype "passive"))
    )
    (net (code "75") (name "/PA10") (class "Default")
      (node (ref "U1") (pin "102") (pinfunction "PA10/TIM1_CH3/U1_RX/OTG_FS_ID/DCMI_D1_102") (pintype "passive"))
    )
    (net (code "76") (name "/PA11") (class "Default")
      (node (ref "R33") (pin "2") (pintype "passive"))
      (node (ref "U1") (pin "103") (pinfunction "PA11/TIM1_CH4/U1_CTS/CAN1_RX/OTG_FS_DM_103") (pintype "passive"))
    )
    (net (code "77") (name "/PA12") (class "Default")
      (node (ref "R32") (pin "2") (pintype "passive"))
      (node (ref "U1") (pin "104") (pinfunction "PA12/TIM1_ETR/U1_RTS/CAN1_TX/OTG_FS_DP_104") (pintype "passive"))
    )
    (net (code "78") (name "/PA15") (class "Default")
      (node (ref "U1") (pin "110") (pinfunction "PA15/JTDI/SPI1_NSS/SPI3_NSS/TIM2_CH1_ETR/I2S3_WS_110") (pintype "passive"))
    )
    (net (code "79") (name "/PB0") (class "Default")
      (node (ref "J3") (pin "3") (pinfunction "INT_3") (pintype "passive"))
      (node (ref "U1") (pin "46") (pinfunction "PB0/TIM1_CH2N/TIM3_CH3/TIM8_CH2N/OTG_HS_ULPI_D1/ETH_MII_RXD2/ADC12_IN8_46") (pintype "passive"))
    )
    (net (code "80") (name "/PB1") (class "Default")
      (node (ref "J3") (pin "2") (pinfunction "RST_2") (pintype "passive"))
      (node (ref "U1") (pin "47") (pinfunction "PB1/TIM1_CH3N/TIM3_CH4/TIM8_CH3N/OTG_HS_INTN/ETH_MII_RXD3/ADC12_IN9_47") (pintype "passive"))
    )
    (net (code "81") (name "/PB5") (class "Default")
      (node (ref "U1") (pin "135") (pinfunction "PB5/TIM3_CH2/SPI1_MOSI/SPI3_MOSI/CAN2_RX/I2C1_SMBA/OTG_HS_ULPI_D7/ETH_PPS_OUT/DCMI_D10/I2S3_SD_135") (pintype "passive"))
    )
    (net (code "82") (name "/PB8") (class "Default")
      (node (ref "U1") (pin "139") (pinfunction "PB8/TIM4_CH3/TIM10_CH1/CAN1_RX/SDIO_D4/ETH_MII_TXD3/I2C1_SCL/DCMI_D6_139") (pintype "passive"))
    )
    (net (code "83") (name "/PB9") (class "Default")
      (node (ref "U1") (pin "140") (pinfunction "PB9/TIM4_CH4/TIM11_CH1/CAN1_TX/SDIO_D5/SPI2_NSS/I2C1_SDA/DCMI_D7/I2S2_WS_140") (pintype "passive"))
    )
    (net (code "84") (name "/PB10") (class "Default")
      (node (ref "U1") (pin "69") (pinfunction "PB10/SPI2_SCK/TIM2_CH3/U3_TX/I2C2_SCL/OTG_HS_ULPI_D3/I2S2_CK_69") (pintype "passive"))
    )
    (net (code "85") (name "/PB11") (class "Default")
      (node (ref "U1") (pin "70") (pinfunction "PB11/TIM2_CH4/U3_RX/I2C2_SDA/HS_ULPI_D4/ETH_MII_TX_EN/ETH_RMII_TX_EN_70") (pintype "passive"))
    )
    (net (code "86") (name "/PB14") (class "Default")
      (node (ref "U1") (pin "75") (pinfunction "PB14/SPI2_MISO/TIM1_CH2N/TIM8_CH2N/TIM12_CH1/U3_RTS/OTG_HS_DM/I2S2ext_SD_75") (pintype "passive"))
    )
    (net (code "87") (name "/PB15") (class "Default")
      (node (ref "U1") (pin "76") (pinfunction "PB15/SPI2_MOSI/TIM1_CH3N/TIM8_CH3N/TIM12_CH2/OTG_HS_DP/I2S2_SD_76") (pintype "passive"))
    )
    (net (code "88") (name "/PC0") (class "Default")
      (node (ref "U1") (pin "26") (pinfunction "PC0/OTG_HS_ULPI_STP/ADC123_IN10_26") (pintype "passive"))
    )
    (net (code "89") (name "/PC1") (class "Default")
      (node (ref "U1") (pin "27") (pinfunction "PC1/ETH_MDC/ADC123_IN11_27") (pintype "passive"))
    )
    (net (code "90") (name "/PC4") (class "Default")
      (node (ref "J3") (pin "7") (pinfunction "SDA_7") (pintype "passive"))
      (node (ref "U1") (pin "44") (pinfunction "PC4/ETH_MII_RXD0/ETH_RMII_RXD0/ADC12_IN14_44") (pintype "passive"))
    )
    (net (code "91") (name "/PC5") (class "Default")
      (node (ref "J3") (pin "6") (pinfunction "SCL_6") (pintype "passive"))
      (node (ref "U1") (pin "45") (pinfunction "PC5/ETH_MII_RXD1/ETH_RMII_RXD1/ADC12_IN15_45") (pintype "passive"))
    )
    (net (code "92") (name "/PC8") (class "Default")
      (node (ref "R15") (pin "1") (pintype "passive"))
      (node (ref "TF_CARD") (pin "7") (pinfunction "DAT0/DO_7") (pintype "passive"))
      (node (ref "U1") (pin "98") (pinfunction "PC8/TIM3_CH3/TIM8_CH3/U6_CK/SDIO_D0/DCMI_D2_98") (pintype "passive"))
    )
    (net (code "93") (name "/PC9") (class "Default")
      (node (ref "R19") (pin "1") (pintype "passive"))
      (node (ref "TF_CARD") (pin "8") (pinfunction "DAT1/IRQ_8") (pintype "passive"))
      (node (ref "U1") (pin "99") (pinfunction "PC9/TIM3_CH4/TIM8_CH4/I2C3_SDA/SDIO_D1/DCMI_D3/MCO2/I2S_CKIN_99") (pintype "passive"))
    )
    (net (code "94") (name "/PC10") (class "Default")
      (node (ref "R18") (pin "1") (pintype "passive"))
      (node (ref "TF_CARD") (pin "1") (pinfunction "DAT2/NC_1") (pintype "passive"))
      (node (ref "U1") (pin "111") (pinfunction "PC10/SPI3_SCK/U3_TX/U4_TX/SDIO_D2/DCMI_D8/I2S3_CK_111") (pintype "passive"))
    )
    (net (code "95") (name "/PC11") (class "Default")
      (node (ref "R17") (pin "1") (pintype "passive"))
      (node (ref "TF_CARD") (pin "2") (pinfunction "CS/DATA3_2") (pintype "passive"))
      (node (ref "U1") (pin "112") (pinfunction "PC11/SPI3_MISO/U3_RX/U4_RX/SDIO_D3/DCMI_D4/I2S3ext_SD_112") (pintype "passive"))
    )
    (net (code "96") (name "/PC12") (class "Default")
      (node (ref "TF_CARD") (pin "5") (pinfunction "CLK_5") (pintype "passive"))
      (node (ref "U1") (pin "113") (pinfunction "PC12/SPI3_MOSI/U3_CK/U5_TX/SDIO_CK/DCMI_D9/I2S3_SD_113") (pintype "passive"))
    )
    (net (code "97") (name "/PC13") (class "Default")
      (node (ref "U1") (pin "7") (pinfunction "PC13/RTC_AF1_7") (pintype "passive"))
    )
    (net (code "98") (name "/PC14") (class "Default")
      (node (ref "C3") (pin "2") (pintype "passive"))
      (node (ref "U1") (pin "8") (pinfunction "PC14-OSC32_IN_8") (pintype "passive"))
      (node (ref "Y2") (pin "1") (pinfunction "OSC1_1") (pintype "passive"))
    )
    (net (code "99") (name "/PC15") (class "Default")
      (node (ref "C4") (pin "1") (pintype "passive"))
      (node (ref "U1") (pin "9") (pinfunction "PC15-OSC32_OUT_9") (pintype "passive"))
      (node (ref "Y2") (pin "2") (pinfunction "OSC2_2") (pintype "passive"))
    )
    (net (code "100") (name "/PD2") (class "Default")
      (node (ref "R16") (pin "1") (pintype "passive"))
      (node (ref "TF_CARD") (pin "3") (pinfunction "CMD_3") (pintype "passive"))
      (node (ref "U1") (pin "116") (pinfunction "PD2/TIM3_ETR/U5_RX/SDIO_CMD/DCMI_D11_116") (pintype "passive"))
    )
    (net (code "101") (name "/PD3") (class "Default")
      (node (ref "U1") (pin "117") (pinfunction "PD3/FSMC_CLK/U2_CTS_117") (pintype "passive"))
    )
    (net (code "102") (name "/PD6") (class "Default")
      (node (ref "U1") (pin "122") (pinfunction "PD6/FSMC_NWAIT/U2_RX_122") (pintype "passive"))
    )
    (net (code "103") (name "/PD7") (class "Default")
      (node (ref "U1") (pin "123") (pinfunction "PD7/FSMC_NE1/FSMC_NCE2/U2_CK_123") (pintype "passive"))
    )
    (net (code "104") (name "/PE2") (class "Default")
      (node (ref "U1") (pin "1") (pinfunction "PE2/TRACECLK/FSMC_A23/ETH_MII_TXD3_1") (pintype "passive"))
    )
    (net (code "105") (name "/PE3") (class "Default")
      (node (ref "U1") (pin "2") (pinfunction "PE3/TRACED0/FSMC_A19_2") (pintype "passive"))
    )
    (net (code "106") (name "/PE4") (class "Default")
      (node (ref "U1") (pin "3") (pinfunction "PE4/TRACED1/FSMC_A20/DCMI_D4_3") (pintype "passive"))
    )
    (net (code "107") (name "/PE5") (class "Default")
      (node (ref "U1") (pin "4") (pinfunction "PE5/TRACED2/FSMC_A21/TIM9_CH1/DCMI_D6_4") (pintype "passive"))
    )
    (net (code "108") (name "/PF6") (class "Default")
      (node (ref "U1") (pin "18") (pinfunction "PF6/TIM10_CH1/FSMC_NIORD/ADC3_IN4_18") (pintype "passive"))
    )
    (net (code "109") (name "/PF7") (class "Default")
      (node (ref "U1") (pin "19") (pinfunction "PF7/TIM11_CH1/FSMC_NREG/ADC3_IN5_19") (pintype "passive"))
    )
    (net (code "110") (name "/PF8") (class "Default")
      (node (ref "U1") (pin "20") (pinfunction "PF8/TIM13_CH1/FSMC_NIOWR/ADC3_IN6_20") (pintype "passive"))
    )
    (net (code "111") (name "/PF9") (class "Default")
      (node (ref "U1") (pin "21") (pinfunction "PF9/TIM14_CH1/FSMC_CD/ADC3_IN7_21") (pintype "passive"))
    )
    (net (code "112") (name "/PF10") (class "Default")
      (node (ref "U1") (pin "22") (pinfunction "PF10/FSMC_INTR/ADC3_IN8_22") (pintype "passive"))
    )
    (net (code "113") (name "/PF11") (class "Default")
      (node (ref "U1") (pin "49") (pinfunction "PF11/DCMI_D12_49") (pintype "passive"))
    )
    (net (code "114") (name "/PG9") (class "Default")
      (node (ref "U1") (pin "124") (pinfunction "PG9/FSMC_NE2/FSMC_NCE3/U6_RX_124") (pintype "passive"))
    )
    (net (code "115") (name "/PG11") (class "Default")
      (node (ref "U1") (pin "126") (pinfunction "PG11/FSMC_NCE4_2/ETH_MII_TX_EN/ETH_RMII_TX_EN_126") (pintype "passive"))
    )
    (net (code "116") (name "/PG13") (class "Default")
      (node (ref "U1") (pin "128") (pinfunction "PG13/FSMC_A24/U6_CTS/ETH_MII_TXD0/ETH_RMII_TXD0_128") (pintype "passive"))
    )
    (net (code "117") (name "/PG14") (class "Default")
      (node (ref "U1") (pin "129") (pinfunction "PG14/FSMC_A25/U6_TX/ETH_MII_TXD1/ETH_RMII_TXD1_129") (pintype "passive"))
    )
    (net (code "118") (name "/PG15") (class "Default")
      (node (ref "U1") (pin "132") (pinfunction "PG15/U6_CTS/DCMI_D13_132") (pintype "passive"))
    )
    (net (code "119") (name "/PJ_G") (class "Default")
      (node (ref "PJ1") (pin "7") (pinfunction "7_7") (pintype "passive"))
    )
    (net (code "120") (name "/PJ_L") (class "Default")
      (node (ref "PJ1") (pin "5") (pinfunction "L_5") (pintype "passive"))
    )
    (net (code "121") (name "/PJ_M") (class "Default")
      (node (ref "PJ1") (pin "8") (pinfunction "8_8") (pintype "passive"))
    )
    (net (code "122") (name "/PJ_R") (class "Default")
      (node (ref "PJ1") (pin "6") (pinfunction "6_6") (pintype "passive"))
    )
    (net (code "123") (name "/PWM_AUDIO") (class "Default")
      (node (ref "C58") (pin "2") (pintype "passive"))
      (node (ref "C59") (pin "2") (pintype "passive"))
    )
    (net (code "124") (name "/RESET") (class "Default")
      (node (ref "C10") (pin "2") (pintype "passive"))
      (node (ref "R3") (pin "1") (pintype "passive"))
      (node (ref "RESET") (pin "1") (pinfunction "1_1") (pintype "passive"))
      (node (ref "TFT1") (pin "8") (pinfunction "RST_8") (pintype "passive"))
      (node (ref "U1") (pin "25") (pinfunction "NRST_25") (pintype "passive"))
    )
    (net (code "125") (name "/VREF") (class "Default")
      (node (ref "C23") (pin "2") (pintype "passive"))
      (node (ref "C24") (pin "2") (pintype "passive"))
      (node (ref "R4") (pin "1") (pintype "passive"))
      (node (ref "U1") (pin "32") (pinfunction "Vref+_32") (pintype "passive"))
      (node (ref "U1") (pin "33") (pinfunction "VDDA_33") (pintype "passive"))
    )
    (net (code "126") (name "/VUSB") (class "Default")
      (node (ref "POWER") (pin "3") (pinfunction "I/O_3") (pintype "passive"))
      (node (ref "USB_HOST") (pin "1") (pinfunction "VCC_1") (pintype "passive"))
    )
    (net (code "127") (name "AGND") (class "Default")
      (node (ref "C26") (pin "1") (pintype "passive"))
      (node (ref "C52") (pin "2") (pintype "passive"))
      (node (ref "C53") (pin "2") (pintype "passive"))
      (node (ref "C56") (pin "1") (pintype "passive"))
      (node (ref "C57") (pin "1") (pintype "passive"))
      (node (ref "PJ1") (pin "4") (pinfunction "GND_4") (pintype "passive"))
      (node (ref "R53") (pin "2") (pintype "passive"))
      (node (ref "R55") (pin "1") (pintype "passive"))
      (node (ref "R56") (pin "1") (pintype "passive"))
      (node (ref "U5") (pin "28") (pinfunction "AGND_28") (pintype "passive"))
    )
    (net (code "128") (name "GND") (class "Default")
      (node (ref "BAT") (pin "2") (pinfunction "DC-_2") (pintype "passive"))
      (node (ref "C1") (pin "1") (pintype "passive"))
      (node (ref "C10") (pin "1") (pintype "passive"))
      (node (ref "C100") (pin "1") (pintype "passive"))
      (node (ref "C101") (pin "1") (pintype "passive"))
      (node (ref "C102") (pin "1") (pintype "passive"))
      (node (ref "C105") (pin "2") (pintype "passive"))
      (node (ref "C11") (pin "1") (pintype "passive"))
      (node (ref "C12") (pin "1") (pintype "passive"))
      (node (ref "C13") (pin "1") (pintype "passive"))
      (node (ref "C14") (pin "1") (pintype "passive"))
      (node (ref "C15") (pin "1") (pintype "passive"))
      (node (ref "C16") (pin "1") (pintype "passive"))
      (node (ref "C17") (pin "1") (pintype "passive"))
      (node (ref "C18") (pin "1") (pintype "passive"))
      (node (ref "C19") (pin "1") (pintype "passive"))
      (node (ref "C2") (pin "1") (pintype "passive"))
      (node (ref "C20") (pin "1") (pintype "passive"))
      (node (ref "C21") (pin "1") (pintype "passive"))
      (node (ref "C22") (pin "1") (pintype "passive"))
      (node (ref "C23") (pin "1") (pintype "passive"))
      (node (ref "C24") (pin "1") (pintype "passive"))
      (node (ref "C29") (pin "2") (pintype "passive"))
      (node (ref "C3") (pin "1") (pintype "passive"))
      (node (ref "C31") (pin "2") (pintype "passive"))
      (node (ref "C36") (pin "2") (pintype "passive"))
      (node (ref "C4") (pin "2") (pintype "passive"))
      (node (ref "C43") (pin "1") (pintype "passive"))
      (node (ref "C44") (pin "2") (pinfunction "GND_2") (pintype "passive"))
      (node (ref "C45") (pin "1") (pintype "passive"))
      (node (ref "C5") (pin "1") (pintype "passive"))
      (node (ref "C50") (pin "1") (pintype "passive"))
      (node (ref "C51") (pin "1") (pintype "passive"))
      (node (ref "C54") (pin "1") (pintype "passive"))
      (node (ref "C55") (pin "1") (pintype "passive"))
      (node (ref "C6") (pin "1") (pintype "passive"))
      (node (ref "C68") (pin "1") (pintype "passive"))
      (node (ref "C69") (pin "1") (pintype "passive"))
      (node (ref "C7") (pin "1") (pintype "passive"))
      (node (ref "C70") (pin "2") (pinfunction "GND_2") (pintype "passive"))
      (node (ref "C8") (pin "2") (pintype "passive"))
      (node (ref "C9") (pin "2") (pintype "passive"))
      (node (ref "C97") (pin "1") (pintype "passive"))
      (node (ref "C98") (pin "1") (pintype "passive"))
      (node (ref "J3") (pin "8") (pinfunction "GND_8") (pintype "passive"))
      (node (ref "KEY0") (pin "2") (pinfunction "2_2") (pintype "passive"))
      (node (ref "P10") (pin "1") (pinfunction "1_1") (pintype "passive"))
      (node (ref "R11") (pin "2") (pintype "passive"))
      (node (ref "R44") (pin "1") (pintype "passive"))
      (node (ref "R46") (pin "2") (pintype "passive"))
      (node (ref "R52") (pin "1") (pintype "passive"))
      (node (ref "R53") (pin "1") (pintype "passive"))
      (node (ref "R6") (pin "2") (pintype "passive"))
      (node (ref "RESET") (pin "2") (pinfunction "2_2") (pintype "passive"))
      (node (ref "TFT1") (pin "1") (pinfunction "GND_1") (pintype "passive"))
      (node (ref "TFT1") (pin "37") (pinfunction "GND_37") (pintype "passive"))
      (node (ref "TF_CARD") (pin "6") (pinfunction "VSS_6") (pintype "passive"))
      (node (ref "U1") (pin "107") (pinfunction "VSS_107") (pintype "passive"))
      (node (ref "U1") (pin "120") (pinfunction "VSS_120") (pintype "passive"))
      (node (ref "U1") (pin "130") (pinfunction "VSS_130") (pintype "passive"))
      (node (ref "U1") (pin "16") (pinfunction "VSS_16") (pintype "passive"))
      (node (ref "U1") (pin "31") (pinfunction "VSSA_31") (pintype "passive"))
      (node (ref "U1") (pin "38") (pinfunction "VSS_38") (pintype "passive"))
      (node (ref "U1") (pin "51") (pinfunction "VSS_51") (pintype "passive"))
      (node (ref "U1") (pin "61") (pinfunction "VSS_61") (pintype "passive"))
      (node (ref "U1") (pin "83") (pinfunction "VSS_83") (pintype "passive"))
      (node (ref "U1") (pin "94") (pinfunction "VSS_94") (pintype "passive"))
      (node (ref "U12") (pin "1") (pinfunction "GND_1") (pintype "passive"))
      (node (ref "U13") (pin "1") (pinfunction "GND_1") (pintype "passive"))
      (node (ref "U16") (pin "2") (pinfunction "GND_2") (pintype "passive"))
      (node (ref "U2") (pin "12") (pinfunction "GND_12") (pintype "passive"))
      (node (ref "U2") (pin "34") (pinfunction "GND_34") (pintype "passive"))
      (node (ref "U3") (pin "1") (pinfunction "A0_1") (pintype "passive"))
      (node (ref "U3") (pin "2") (pinfunction "A1_2") (pintype "passive"))
      (node (ref "U3") (pin "3") (pinfunction "A2_3") (pintype "passive"))
      (node (ref "U3") (pin "4") (pinfunction "GND_4") (pintype "passive"))
      (node (ref "U3") (pin "7") (pinfunction "WP_7") (pintype "passive"))
      (node (ref "U4") (pin "4") (pinfunction "GND_4") (pintype "passive"))
      (node (ref "U5") (pin "12") (pinfunction "DGND_12") (pintype "passive"))
      (node (ref "U5") (pin "24") (pinfunction "SPKGND_24") (pintype "passive"))
      (node (ref "U5") (pin "33") (pinfunction "GNDPAD_33") (pintype "passive"))
      (node (ref "USB_HOST") (pin "5") (pinfunction "GND_5") (pintype "passive"))
      (node (ref "USB_HOST") (pin "6") (pinfunction "Shell1_6") (pintype "passive"))
      (node (ref "USB_HOST") (pin "7") (pinfunction "Shell2_7") (pintype "passive"))
      (node (ref "USB_HOST") (pin "8") (pinfunction "Shell3_8") (pintype "passive"))
      (node (ref "USB_HOST") (pin "9") (pinfunction "Shell4_9") (pintype "passive"))
      (node (ref "Y1") (pin "2") (pinfunction "GND_2") (pintype "passive"))
    )
    (net (code "129") (name "Net-(BAT-DC+)") (class "Default")
      (node (ref "BAT") (pin "1") (pinfunction "DC+_1") (pintype "passive"))
      (node (ref "D1") (pin "2") (pintype "passive"))
      (node (ref "U1") (pin "6") (pinfunction "VBAT_6") (pintype "passive"))
    )
    (net (code "130") (name "Net-(C66-VCC)") (class "Default")
      (node (ref "C66") (pin "1") (pinfunction "VCC_1") (pintype "passive"))
      (node (ref "U5") (pin "29") (pinfunction "ROUT1_29") (pintype "passive"))
    )
    (net (code "131") (name "Net-(C67-VCC)") (class "Default")
      (node (ref "C67") (pin "1") (pinfunction "VCC_1") (pintype "passive"))
      (node (ref "U5") (pin "30") (pinfunction "LOUT1_30") (pintype "passive"))
    )
    (net (code "132") (name "Net-(DS1-A)") (class "Default")
      (node (ref "DS1") (pin "1") (pinfunction "A_1") (pintype "passive"))
      (node (ref "R20") (pin "2") (pintype "passive"))
    )
    (net (code "133") (name "Net-(J3-VDD)") (class "Default")
      (node (ref "C101") (pin "2") (pintype "passive"))
      (node (ref "C102") (pin "2") (pintype "passive"))
      (node (ref "J3") (pin "1") (pinfunction "VDD_1") (pintype "passive"))
      (node (ref "R47") (pin "1") (pintype "passive"))
    )
    (net (code "134") (name "Net-(MIC-GND)") (class "Default")
      (node (ref "C63") (pin "2") (pintype "passive"))
      (node (ref "C65") (pin "2") (pintype "passive"))
      (node (ref "MIC") (pin "2") (pinfunction "GND_2") (pintype "passive"))
      (node (ref "R56") (pin "2") (pintype "passive"))
    )
    (net (code "135") (name "Net-(MIC-VCC)") (class "Default")
      (node (ref "C26") (pin "2") (pintype "passive"))
      (node (ref "C62") (pin "2") (pintype "passive"))
      (node (ref "C64") (pin "2") (pintype "passive"))
      (node (ref "MIC") (pin "1") (pinfunction "VCC_1") (pintype "passive"))
      (node (ref "R54") (pin "2") (pintype "passive"))
      (node (ref "R55") (pin "2") (pintype "passive"))
    )
    (net (code "136") (name "Net-(U1-PDR_ON)") (class "Default")
      (node (ref "R8") (pin "2") (pintype "passive"))
      (node (ref "U1") (pin "143") (pinfunction "PDR_ON_143") (pintype "passive"))
    )
    (net (code "137") (name "Net-(U1-PH0-OSC_IN)") (class "Default")
      (node (ref "C7") (pin "2") (pintype "passive"))
      (node (ref "U1") (pin "23") (pinfunction "PH0-OSC_IN_23") (pintype "passive"))
      (node (ref "Y1") (pin "3") (pinfunction "OSC2_3") (pintype "passive"))
    )
    (net (code "138") (name "Net-(U1-PH1-OSC_OUT)") (class "Default")
      (node (ref "C6") (pin "2") (pintype "passive"))
      (node (ref "U1") (pin "24") (pinfunction "PH1-OSC_OUT_24") (pintype "passive"))
      (node (ref "Y1") (pin "1") (pinfunction "OSC1_1") (pintype "passive"))
    )
    (net (code "139") (name "Net-(U1-Vcap_1)") (class "Default")
      (node (ref "C8") (pin "1") (pintype "passive"))
      (node (ref "U1") (pin "71") (pinfunction "Vcap_1_71") (pintype "passive"))
    )
    (net (code "140") (name "Net-(U1-Vcap_2)") (class "Default")
      (node (ref "C9") (pin "1") (pintype "passive"))
      (node (ref "U1") (pin "106") (pinfunction "Vcap_2_106") (pintype "passive"))
    )
    (net (code "141") (name "Net-(U5-AUXL)") (class "Default")
      (node (ref "C58") (pin "1") (pintype "passive"))
      (node (ref "U5") (pin "19") (pinfunction "AUXL_19") (pintype "passive"))
    )
    (net (code "142") (name "Net-(U5-AUXR)") (class "Default")
      (node (ref "C59") (pin "1") (pintype "passive"))
      (node (ref "U5") (pin "20") (pinfunction "AUXR_20") (pintype "passive"))
    )
    (net (code "143") (name "Net-(U5-DBVDD)") (class "Default")
      (node (ref "C54") (pin "2") (pintype "passive"))
      (node (ref "C55") (pin "2") (pintype "passive"))
      (node (ref "R51") (pin "1") (pintype "passive"))
      (node (ref "U5") (pin "13") (pinfunction "DCVDD_13") (pintype "passive"))
      (node (ref "U5") (pin "14") (pinfunction "DBVDD_14") (pintype "passive"))
    )
    (net (code "144") (name "Net-(U5-L2{slash}GPIO2)") (class "Default")
      (node (ref "C60") (pin "1") (pintype "passive"))
      (node (ref "U5") (pin "3") (pinfunction "L2/GPIO2_3") (pintype "passive"))
    )
    (net (code "145") (name "Net-(U5-LIN)") (class "Default")
      (node (ref "C63") (pin "1") (pintype "passive"))
      (node (ref "U5") (pin "2") (pinfunction "LIN_2") (pintype "passive"))
    )
    (net (code "146") (name "Net-(U5-LIP)") (class "Default")
      (node (ref "C62") (pin "1") (pintype "passive"))
      (node (ref "U5") (pin "1") (pinfunction "LIP_1") (pintype "passive"))
    )
    (net (code "147") (name "Net-(U5-LOUT2)") (class "Default")
      (node (ref "SP-") (pin "1") (pinfunction "1_1") (pintype "passive"))
      (node (ref "U5") (pin "25") (pinfunction "LOUT2_25") (pintype "passive"))
    )
    (net (code "148") (name "Net-(U5-MICBIAS)") (class "Default")
      (node (ref "C57") (pin "2") (pintype "passive"))
      (node (ref "R54") (pin "1") (pintype "passive"))
      (node (ref "U5") (pin "32") (pinfunction "MICBIAS_32") (pintype "passive"))
    )
    (net (code "149") (name "Net-(U5-MODE)") (class "Default")
      (node (ref "R52") (pin "2") (pintype "passive"))
      (node (ref "U5") (pin "18") (pinfunction "MODE_18") (pintype "passive"))
    )
    (net (code "150") (name "Net-(U5-R2{slash}GPIO3)") (class "Default")
      (node (ref "C61") (pin "1") (pintype "passive"))
      (node (ref "U5") (pin "6") (pinfunction "R2/GPIO3_6") (pintype "passive"))
    )
    (net (code "151") (name "Net-(U5-RIN)") (class "Default")
      (node (ref "C65") (pin "1") (pintype "passive"))
      (node (ref "U5") (pin "5") (pinfunction "RIN_5") (pintype "passive"))
    )
    (net (code "152") (name "Net-(U5-RIP)") (class "Default")
      (node (ref "C64") (pin "1") (pintype "passive"))
      (node (ref "U5") (pin "4") (pinfunction "RIP_4") (pintype "passive"))
    )
    (net (code "153") (name "Net-(U5-ROUT2)") (class "Default")
      (node (ref "SP+") (pin "1") (pinfunction "1_1") (pintype "passive"))
      (node (ref "U5") (pin "23") (pinfunction "ROUT2_23") (pintype "passive"))
    )
    (net (code "154") (name "Net-(U5-SPKVDD)") (class "Default")
      (node (ref "C50") (pin "2") (pintype "passive"))
      (node (ref "C51") (pin "2") (pintype "passive"))
      (node (ref "R50") (pin "1") (pintype "passive"))
      (node (ref "U5") (pin "26") (pinfunction "SPKVDD_26") (pintype "passive"))
    )
    (net (code "155") (name "Net-(U5-VMID)") (class "Default")
      (node (ref "C56") (pin "2") (pintype "passive"))
      (node (ref "U5") (pin "27") (pinfunction "VMID_27") (pintype "passive"))
    )
    (net (code "156") (name "Net-(U16-EN)") (class "Default")
      (node (ref "R45") (pin "1") (pintype "passive"))
      (node (ref "R46") (pin "1") (pintype "passive"))
      (node (ref "U16") (pin "4") (pinfunction "EN_4") (pintype "passive"))
    )
    (net (code "157") (name "Net-(U16-IN)") (class "Default")
      (node (ref "C98") (pin "2") (pintype "passive"))
      (node (ref "R43") (pin "1") (pintype "passive"))
      (node (ref "U16") (pin "5") (pinfunction "IN_5") (pintype "passive"))
    )
    (net (code "158") (name "Net-(U16-SW)") (class "Default")
      (node (ref "D3") (pin "1") (pintype "passive"))
      (node (ref "L7") (pin "1") (pintype "passive"))
      (node (ref "U16") (pin "1") (pinfunction "SW_1") (pintype "passive"))
    )
    (net (code "159") (name "Net-(USB_HOST-D+)") (class "Default")
      (node (ref "R32") (pin "1") (pintype "passive"))
      (node (ref "USB_HOST") (pin "3") (pinfunction "D+_3") (pintype "passive"))
    )
    (net (code "160") (name "Net-(USB_HOST-D-)") (class "Default")
      (node (ref "R33") (pin "1") (pintype "passive"))
      (node (ref "USB_HOST") (pin "2") (pinfunction "D-_2") (pintype "passive"))
    )
    (net (code "161") (name "VCC3.3") (class "Default")
      (node (ref "C1") (pin "2") (pintype "passive"))
      (node (ref "C100") (pin "2") (pintype "passive"))
      (node (ref "C11") (pin "2") (pintype "passive"))
      (node (ref "C12") (pin "2") (pintype "passive"))
      (node (ref "C13") (pin "2") (pintype "passive"))
      (node (ref "C14") (pin "2") (pintype "passive"))
      (node (ref "C15") (pin "2") (pintype "passive"))
      (node (ref "C16") (pin "2") (pintype "passive"))
      (node (ref "C17") (pin "2") (pintype "passive"))
      (node (ref "C18") (pin "2") (pintype "passive"))
      (node (ref "C19") (pin "2") (pintype "passive"))
      (node (ref "C2") (pin "2") (pintype "passive"))
      (node (ref "C20") (pin "2") (pintype "passive"))
      (node (ref "C21") (pin "2") (pintype "passive"))
      (node (ref "C22") (pin "2") (pintype "passive"))
      (node (ref "C29") (pin "1") (pintype "passive"))
      (node (ref "C31") (pin "1") (pintype "passive"))
      (node (ref "C36") (pin "1") (pintype "passive"))
      (node (ref "C43") (pin "2") (pintype "passive"))
      (node (ref "C44") (pin "1") (pinfunction "VCC_1") (pintype "passive"))
      (node (ref "C5") (pin "2") (pintype "passive"))
      (node (ref "D1") (pin "1") (pintype "passive"))
      (node (ref "P10") (pin "4") (pinfunction "4_4") (pintype "passive"))
      (node (ref "R1") (pin "2") (pintype "passive"))
      (node (ref "R15") (pin "2") (pintype "passive"))
      (node (ref "R16") (pin "2") (pintype "passive"))
      (node (ref "R17") (pin "2") (pintype "passive"))
      (node (ref "R18") (pin "2") (pintype "passive"))
      (node (ref "R19") (pin "2") (pintype "passive"))
      (node (ref "R20") (pin "1") (pintype "passive"))
      (node (ref "R3") (pin "2") (pintype "passive"))
      (node (ref "R4") (pin "2") (pintype "passive"))
      (node (ref "R47") (pin "2") (pintype "passive"))
      (node (ref "R5") (pin "2") (pintype "passive"))
      (node (ref "R51") (pin "2") (pintype "passive"))
      (node (ref "R8") (pin "1") (pintype "passive"))
      (node (ref "TFT1") (pin "2") (pinfunction "VDD_2") (pintype "passive"))
      (node (ref "TFT1") (pin "3") (pinfunction "IOVCC_3") (pintype "passive"))
      (node (ref "TF_CARD") (pin "4") (pinfunction "VDD_4") (pintype "passive"))
      (node (ref "U1") (pin "108") (pinfunction "VDD_108") (pintype "passive"))
      (node (ref "U1") (pin "121") (pinfunction "VDD_121") (pintype "passive"))
      (node (ref "U1") (pin "131") (pinfunction "VDD_131") (pintype "passive"))
      (node (ref "U1") (pin "144") (pinfunction "VDD_144") (pintype "passive"))
      (node (ref "U1") (pin "17") (pinfunction "VDD_17") (pintype "passive"))
      (node (ref "U1") (pin "30") (pinfunction "VDD_30") (pintype "passive"))
      (node (ref "U1") (pin "39") (pinfunction "VDD_39") (pintype "passive"))
      (node (ref "U1") (pin "52") (pinfunction "VDD_52") (pintype "passive"))
      (node (ref "U1") (pin "62") (pinfunction "VDD_62") (pintype "passive"))
      (node (ref "U1") (pin "72") (pinfunction "VDD_72") (pintype "passive"))
      (node (ref "U1") (pin "84") (pinfunction "VDD_84") (pintype "passive"))
      (node (ref "U1") (pin "95") (pinfunction "VDD_95") (pintype "passive"))
      (node (ref "U12") (pin "2") (pinfunction "OUT_2") (pintype "passive"))
      (node (ref "U12") (pin "4") (pinfunction "OUT_4") (pintype "passive"))
      (node (ref "U2") (pin "11") (pinfunction "VDD_11") (pintype "passive"))
      (node (ref "U2") (pin "33") (pinfunction "VDD_33") (pintype "passive"))
      (node (ref "U3") (pin "8") (pinfunction "VCC1_8") (pintype "passive"))
      (node (ref "U4") (pin "3") (pinfunction "WP#_3") (pintype "passive"))
      (node (ref "U4") (pin "7") (pinfunction "HOLD_7") (pintype "passive"))
      (node (ref "U4") (pin "8") (pinfunction "VCC_8") (pintype "passive"))
    )
    (net (code "162") (name "VCC3.3A") (class "Default")
      (node (ref "C52") (pin "1") (pintype "passive"))
      (node (ref "C53") (pin "1") (pintype "passive"))
      (node (ref "C69") (pin "2") (pintype "passive"))
      (node (ref "C70") (pin "1") (pinfunction "VCC_1") (pintype "passive"))
      (node (ref "U13") (pin "2") (pinfunction "OUT_2") (pintype "passive"))
      (node (ref "U13") (pin "4") (pinfunction "OUT_4") (pintype "passive"))
      (node (ref "U5") (pin "31") (pinfunction "AVDD_31") (pintype "passive"))
    )
    (net (code "163") (name "VCC5") (class "Default")
      (node (ref "C45") (pin "2") (pintype "passive"))
      (node (ref "C68") (pin "2") (pintype "passive"))
      (node (ref "C97") (pin "2") (pintype "passive"))
      (node (ref "L7") (pin "2") (pintype "passive"))
      (node (ref "POWER") (pin "2") (pinfunction "TAP_2") (pintype "passive"))
      (node (ref "R43") (pin "2") (pintype "passive"))
      (node (ref "R50") (pin "2") (pintype "passive"))
      (node (ref "U12") (pin "3") (pinfunction "IN_3") (pintype "passive"))
      (node (ref "U13") (pin "3") (pinfunction "IN_3") (pintype "passive"))
    )
    (net (code "164") (name "unconnected-(J3-GND-Pad9)") (class "Default")
      (node (ref "J3") (pin "9") (pinfunction "GND_9") (pintype "passive"))
    )
    (net (code "165") (name "unconnected-(J3-GND-Pad10)") (class "Default")
      (node (ref "J3") (pin "10") (pinfunction "GND_10") (pintype "passive"))
    )
    (net (code "166") (name "unconnected-(J3-NC-Pad4)") (class "Default")
      (node (ref "J3") (pin "4") (pinfunction "NC_4") (pintype "passive"))
    )
    (net (code "167") (name "unconnected-(J3-NC-Pad5)") (class "Default")
      (node (ref "J3") (pin "5") (pinfunction "NC_5") (pintype "passive"))
    )
    (net (code "168") (name "unconnected-(POWER-GND-Pad4)") (class "Default")
      (node (ref "POWER") (pin "4") (pinfunction "GND_4") (pintype "passive"))
    )
    (net (code "169") (name "unconnected-(POWER-GND-Pad5)") (class "Default")
      (node (ref "POWER") (pin "5") (pinfunction "GND_5") (pintype "passive"))
    )
    (net (code "170") (name "unconnected-(POWER-I{slash}O-Pad1)") (class "Default")
      (node (ref "POWER") (pin "1") (pinfunction "I/O_1") (pintype "passive"))
    )
    (net (code "171") (name "unconnected-(TFT1-NC-Pad25)") (class "Default")
      (node (ref "TFT1") (pin "25") (pinfunction "NC_25") (pintype "passive"))
    )
    (net (code "172") (name "unconnected-(TFT1-NC-Pad30)") (class "Default")
      (node (ref "TFT1") (pin "30") (pinfunction "NC_30") (pintype "passive"))
    )
    (net (code "173") (name "unconnected-(TFT1-NC-Pad31)") (class "Default")
      (node (ref "TFT1") (pin "31") (pinfunction "NC_31") (pintype "passive"))
    )
    (net (code "174") (name "unconnected-(TFT1-NC-Pad32)") (class "Default")
      (node (ref "TFT1") (pin "32") (pinfunction "NC_32") (pintype "passive"))
    )
    (net (code "175") (name "unconnected-(TFT1-NC-Pad33)") (class "Default")
      (node (ref "TFT1") (pin "33") (pinfunction "NC_33") (pintype "passive"))
    )
    (net (code "176") (name "unconnected-(TFT1-NC-Pad36)") (class "Default")
      (node (ref "TFT1") (pin "36") (pinfunction "NC_36") (pintype "passive"))
    )
    (net (code "177") (name "unconnected-(TFT1-X+-Pad29)") (class "Default")
      (node (ref "TFT1") (pin "29") (pinfunction "X+_29") (pintype "passive"))
    )
    (net (code "178") (name "unconnected-(TFT1-X--Pad27)") (class "Default")
      (node (ref "TFT1") (pin "27") (pinfunction "X-_27") (pintype "passive"))
    )
    (net (code "179") (name "unconnected-(TFT1-Y+-Pad28)") (class "Default")
      (node (ref "TFT1") (pin "28") (pinfunction "Y+_28") (pintype "passive"))
    )
    (net (code "180") (name "unconnected-(TFT1-Y--Pad26)") (class "Default")
      (node (ref "TFT1") (pin "26") (pinfunction "Y-_26") (pintype "passive"))
    )
    (net (code "181") (name "unconnected-(U5-CSB{slash}GPIO1-Pad15)") (class "Default")
      (node (ref "U5") (pin "15") (pinfunction "CSB/GPIO1_15") (pintype "passive"))
    )
    (net (code "182") (name "unconnected-(U5-OUT3-Pad22)") (class "Default")
      (node (ref "U5") (pin "22") (pinfunction "OUT3_22") (pintype "passive"))
    )
    (net (code "183") (name "unconnected-(U5-OUT4-Pad21)") (class "Default")
      (node (ref "U5") (pin "21") (pinfunction "OUT4_21") (pintype "passive"))
    )
    (net (code "184") (name "unconnected-(USB_HOST-ID-Pad4)") (class "Default")
      (node (ref "USB_HOST") (pin "4") (pinfunction "ID_4") (pintype "passive"))
    )
  )
)
